# PCM5102.net
KiCad netlist of a schematic drawn in Altium Designer
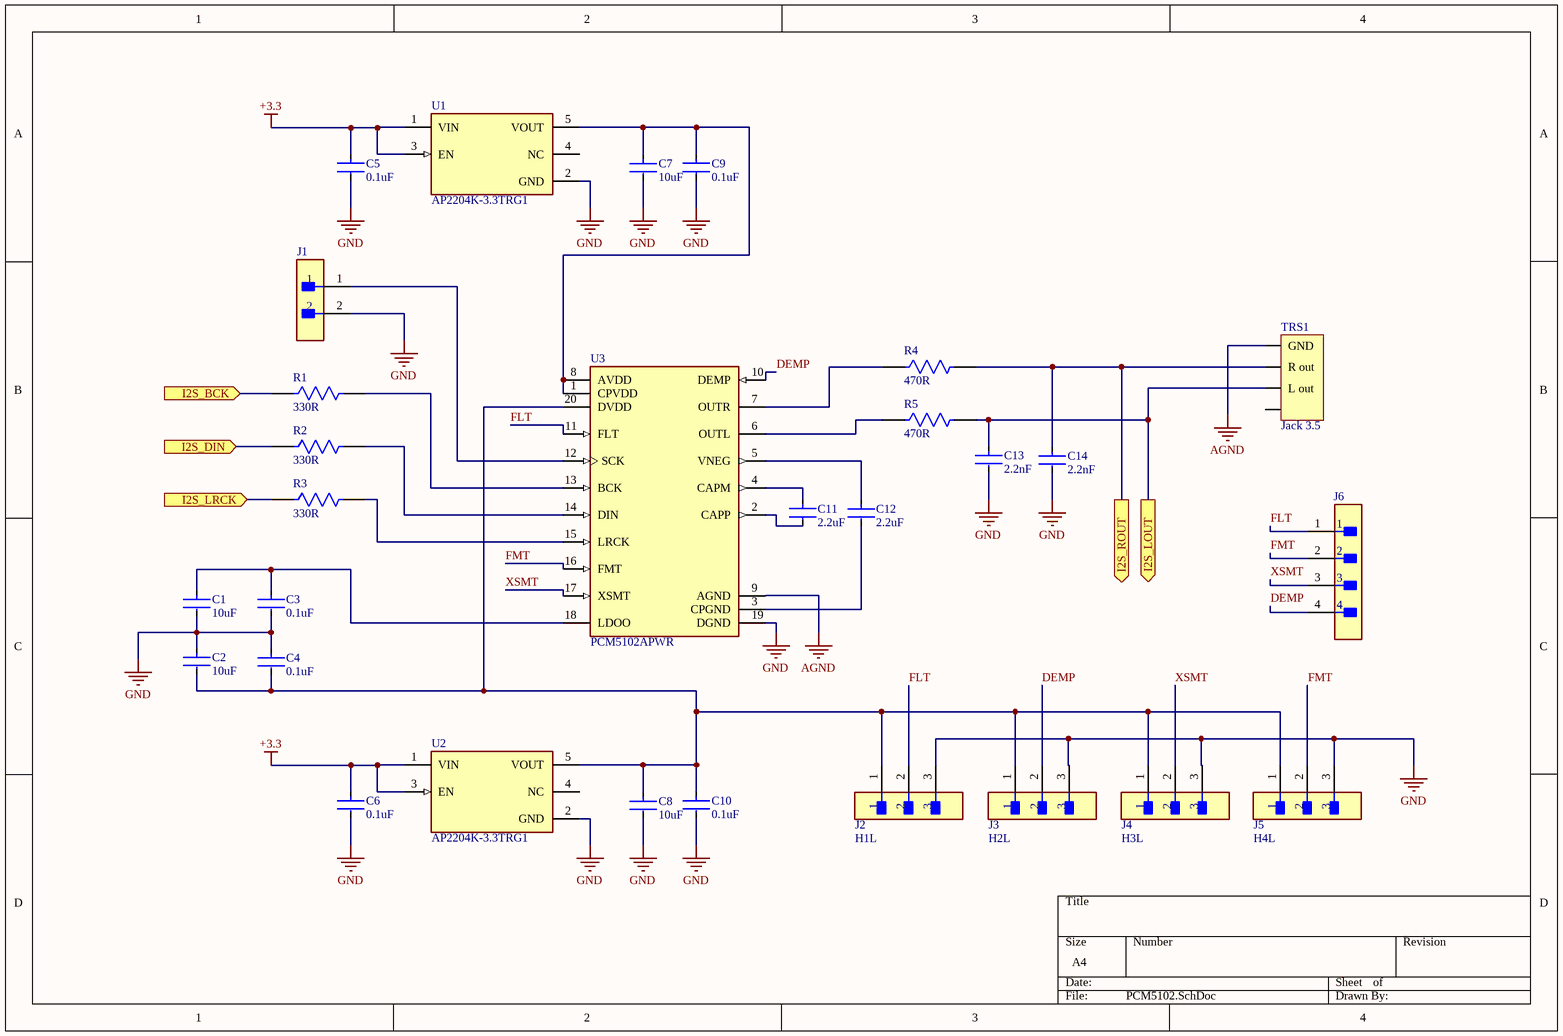
[diagram p0: PCM5102.SchDoc]

(export (version "E")
  (design (tool "Eeschema 10.0.6"))
  (components
    (comp (ref "C1")
      (value "10uF")
      (footprint "FP-CL21-IPC_C")
      (description "CL21 Series 0805 47nF 50V ±5% Tolerance X7R Multilayer Ceramic Chip Capacitor")
      (fields (field (name "TOLERANCE") "5%"))
      (libsource (lib "Altium Content Vault") (part "b4654b650e69147ec39a6b967a45e02"))
    )
    (comp (ref "C2")
      (value "10uF")
      (footprint "FP-CL21-IPC_C")
      (description "CL21 Series 0805 47nF 50V ±5% Tolerance X7R Multilayer Ceramic Chip Capacitor")
      (fields (field (name "TOLERANCE") "5%"))
      (libsource (lib "Altium Content Vault") (part "b4654b650e69147ec39a6b967a45e02"))
    )
    (comp (ref "C3")
      (value "0.1uF")
      (footprint "FP-CL21-IPC_C")
      (description "CL21 Series 0805 47nF 50V ±5% Tolerance X7R Multilayer Ceramic Chip Capacitor")
      (fields (field (name "TOLERANCE") "5%"))
      (libsource (lib "Altium Content Vault") (part "b4654b650e69147ec39a6b967a45e02"))
    )
    (comp (ref "C4")
      (value "0.1uF")
      (footprint "FP-CL21-IPC_C")
      (description "CL21 Series 0805 47nF 50V ±5% Tolerance X7R Multilayer Ceramic Chip Capacitor")
      (fields (field (name "TOLERANCE") "5%"))
      (libsource (lib "Altium Content Vault") (part "b4654b650e69147ec39a6b967a45e02"))
    )
    (comp (ref "C5")
      (value "0.1uF")
      (footprint "FP-CL21-IPC_C")
      (description "CL21 Series 0805 47nF 50V ±5% Tolerance X7R Multilayer Ceramic Chip Capacitor")
      (fields (field (name "TOLERANCE") "5%"))
      (libsource (lib "Altium Content Vault") (part "b4654b650e69147ec39a6b967a45e02"))
    )
    (comp (ref "C6")
      (value "0.1uF")
      (footprint "FP-CL21-IPC_C")
      (description "CL21 Series 0805 47nF 50V ±5% Tolerance X7R Multilayer Ceramic Chip Capacitor")
      (fields (field (name "TOLERANCE") "5%"))
      (libsource (lib "Altium Content Vault") (part "b4654b650e69147ec39a6b967a45e02"))
    )
    (comp (ref "C7")
      (value "10uF")
      (footprint "FP-CL21-IPC_C")
      (description "CL21 Series 0805 47nF 50V ±5% Tolerance X7R Multilayer Ceramic Chip Capacitor")
      (fields (field (name "TOLERANCE") "5%"))
      (libsource (lib "Altium Content Vault") (part "b4654b650e69147ec39a6b967a45e02"))
    )
    (comp (ref "C8")
      (value "10uF")
      (footprint "FP-CL21-IPC_C")
      (description "CL21 Series 0805 47nF 50V ±5% Tolerance X7R Multilayer Ceramic Chip Capacitor")
      (fields (field (name "TOLERANCE") "5%"))
      (libsource (lib "Altium Content Vault") (part "b4654b650e69147ec39a6b967a45e02"))
    )
    (comp (ref "C9")
      (value "0.1uF")
      (footprint "FP-CL21-IPC_C")
      (description "CL21 Series 0805 47nF 50V ±5% Tolerance X7R Multilayer Ceramic Chip Capacitor")
      (fields (field (name "TOLERANCE") "5%"))
      (libsource (lib "Altium Content Vault") (part "b4654b650e69147ec39a6b967a45e02"))
    )
    (comp (ref "C10")
      (value "0.1uF")
      (footprint "FP-CL21-IPC_C")
      (description "CL21 Series 0805 47nF 50V ±5% Tolerance X7R Multilayer Ceramic Chip Capacitor")
      (fields (field (name "TOLERANCE") "5%"))
      (libsource (lib "Altium Content Vault") (part "b4654b650e69147ec39a6b967a45e02"))
    )
    (comp (ref "C11")
      (value "2.2uF")
      (footprint "FP-CL21-IPC_C")
      (description "CL21 Series 0805 47nF 50V ±5% Tolerance X7R Multilayer Ceramic Chip Capacitor")
      (fields (field (name "TOLERANCE") "5%"))
      (libsource (lib "Altium Content Vault") (part "b4654b650e69147ec39a6b967a45e02"))
    )
    (comp (ref "C12")
      (value "2.2uF")
      (footprint "FP-CL21-IPC_C")
      (description "CL21 Series 0805 47nF 50V ±5% Tolerance X7R Multilayer Ceramic Chip Capacitor")
      (fields (field (name "TOLERANCE") "5%"))
      (libsource (lib "Altium Content Vault") (part "b4654b650e69147ec39a6b967a45e02"))
    )
    (comp (ref "C13")
      (value "2.2nF")
      (footprint "FP-CL21-IPC_C")
      (description "CL21 Series 0805 47nF 50V ±5% Tolerance X7R Multilayer Ceramic Chip Capacitor")
      (fields (field (name "TOLERANCE") "5%"))
      (libsource (lib "Altium Content Vault") (part "b4654b650e69147ec39a6b967a45e02"))
    )
    (comp (ref "C14")
      (value "2.2nF")
      (footprint "FP-CL21-IPC_C")
      (description "CL21 Series 0805 47nF 50V ±5% Tolerance X7R Multilayer Ceramic Chip Capacitor")
      (fields (field (name "TOLERANCE") "5%"))
      (libsource (lib "Altium Content Vault") (part "b4654b650e69147ec39a6b967a45e02"))
    )
    (comp (ref "J1")
      (value "M22-2510205")
      (footprint "FP-M22-2510205-MFG")
      (description "CONN HEADER VERT 2POS 2MM")
      (fields
        (field (name "MANUFACTURER") "Harwin")
        (field (name "OCTOPART") "https://octopart.com/m22-2510205-harwin-2538221")
      )
      (libsource (lib "Altium Content Vault") (part "3bc925449376181038e59eaffc5286c"))
    )
    (comp (ref "J2")
      (value "H1L")
      (footprint "FP-951103-8622-AR-MFG")
      (description "CONN HEADER VERT 3POS 2MM")
      (fields
        (field (name "MANUFACTURER PART NUMBER") "951103-8622-AR")
        (field (name "OCTOPART") "https://octopart.com/951103-8622-ar-3m-14400669")
      )
      (libsource (lib "Altium Content Vault") (part "0d3f023dd272f625e17a2be33dea85f"))
    )
    (comp (ref "J3")
      (value "H2L")
      (footprint "FP-951103-8622-AR-MFG")
      (description "CONN HEADER VERT 3POS 2MM")
      (fields
        (field (name "MANUFACTURER PART NUMBER") "951103-8622-AR")
        (field (name "OCTOPART") "https://octopart.com/951103-8622-ar-3m-14400669")
      )
      (libsource (lib "Altium Content Vault") (part "0d3f023dd272f625e17a2be33dea85f"))
    )
    (comp (ref "J4")
      (value "H3L")
      (footprint "FP-951103-8622-AR-MFG")
      (description "CONN HEADER VERT 3POS 2MM")
      (fields
        (field (name "MANUFACTURER PART NUMBER") "951103-8622-AR")
        (field (name "OCTOPART") "https://octopart.com/951103-8622-ar-3m-14400669")
      )
      (libsource (lib "Altium Content Vault") (part "0d3f023dd272f625e17a2be33dea85f"))
    )
    (comp (ref "J5")
      (value "H4L")
      (footprint "FP-951103-8622-AR-MFG")
      (description "CONN HEADER VERT 3POS 2MM")
      (fields
        (field (name "MANUFACTURER PART NUMBER") "951103-8622-AR")
        (field (name "OCTOPART") "https://octopart.com/951103-8622-ar-3m-14400669")
      )
      (libsource (lib "Altium Content Vault") (part "0d3f023dd272f625e17a2be33dea85f"))
    )
    (comp (ref "J6")
      (value "M20-9990445")
      (footprint "FP-M20-9990445-MFG")
      (description "M20-9990445 Conn Unshrouded Header HDR 4 POS 2.54mm Solder ST Thru-Hole Bulk/Loose")
      (libsource (lib "Altium Content Vault") (part "299a8cea1bdcbc3624fe62c390fa72c"))
    )
    (comp (ref "R1")
      (value "330R")
      (footprint "FP-RP732A-IPC_C")
      (fields (field (name "TOLERANCE") "0.1%"))
      (libsource (lib "Altium Content Vault") (part "1029c3af85768c4190bb7ad29bc67b5"))
    )
    (comp (ref "R2")
      (value "330R")
      (footprint "FP-RP732A-IPC_C")
      (fields (field (name "TOLERANCE") "0.1%"))
      (libsource (lib "Altium Content Vault") (part "1029c3af85768c4190bb7ad29bc67b5"))
    )
    (comp (ref "R3")
      (value "330R")
      (footprint "FP-RP732A-IPC_C")
      (fields (field (name "TOLERANCE") "0.1%"))
      (libsource (lib "Altium Content Vault") (part "1029c3af85768c4190bb7ad29bc67b5"))
    )
    (comp (ref "R4")
      (value "470R")
      (footprint "FP-RP732A-IPC_C")
      (fields (field (name "TOLERANCE") "0.1%"))
      (libsource (lib "Altium Content Vault") (part "1029c3af85768c4190bb7ad29bc67b5"))
    )
    (comp (ref "R5")
      (value "470R")
      (footprint "FP-RP732A-IPC_C")
      (fields (field (name "TOLERANCE") "0.1%"))
      (libsource (lib "Altium Content Vault") (part "1029c3af85768c4190bb7ad29bc67b5"))
    )
    (comp (ref "TRS1")
      (value "Jack 3.5")
      (footprint "PJ-327A")
      (libsource (lib "Schemati_design") (part "PJ327A"))
    )
    (comp (ref "U1")
      (value "AP2204K-3.3TRG1")
      (footprint "FP-SOT25-IPC_C")
      (description "IC REG LINEAR 3.3V 150MA SOT23-5")
      (libsource (lib "Altium Content Vault") (part "038a824adfd04a965d73cdd9fb88cf2"))
    )
    (comp (ref "U2")
      (value "AP2204K-3.3TRG1")
      (footprint "FP-SOT25-IPC_C")
      (description "IC REG LINEAR 3.3V 150MA SOT23-5")
      (libsource (lib "Altium Content Vault") (part "038a824adfd04a965d73cdd9fb88cf2"))
    )
    (comp (ref "U3")
      (value "PCM5102APWR")
      (footprint "FP-PW0020A-IPC_A")
      (description "IC DAC 16/24/32BIT 384K 20TSSOP")
      (libsource (lib "Altium Content Vault") (part "831166dc95f78e7a0e4986cce343839"))
    )
  )
  (nets
    (net (code "1") (name "+3.3") (class "Default")
      (node (ref "C5") (pin "1") (pinfunction "1_1") (pintype "passive"))
      (node (ref "C6") (pin "1") (pinfunction "1_1") (pintype "passive"))
      (node (ref "U1") (pin "1") (pinfunction "VIN_1") (pintype "power_in"))
      (node (ref "U1") (pin "3") (pinfunction "EN_3") (pintype "input"))
      (node (ref "U2") (pin "1") (pinfunction "VIN_1") (pintype "power_in"))
      (node (ref "U2") (pin "3") (pinfunction "EN_3") (pintype "input"))
    )
    (net (code "2") (name "/DEMP") (class "Default")
      (node (ref "J3") (pin "2") (pinfunction "2_2") (pintype "passive"))
      (node (ref "J6") (pin "4") (pinfunction "4_4") (pintype "passive"))
      (node (ref "U3") (pin "10") (pinfunction "DEMP_10") (pintype "input"))
    )
    (net (code "3") (name "/FLT") (class "Default")
      (node (ref "J2") (pin "2") (pinfunction "2_2") (pintype "passive"))
      (node (ref "J6") (pin "1") (pinfunction "1_1") (pintype "passive"))
      (node (ref "U3") (pin "11") (pinfunction "FLT_11") (pintype "input"))
    )
    (net (code "4") (name "/FMT") (class "Default")
      (node (ref "J5") (pin "2") (pinfunction "2_2") (pintype "passive"))
      (node (ref "J6") (pin "2") (pinfunction "2_2") (pintype "passive"))
      (node (ref "U3") (pin "16") (pinfunction "FMT_16") (pintype "input"))
    )
    (net (code "5") (name "/I2S_BCK") (class "Default")
      (node (ref "R1") (pin "1") (pinfunction "1_1") (pintype "passive"))
    )
    (net (code "6") (name "/I2S_DIN") (class "Default")
      (node (ref "R2") (pin "1") (pinfunction "1_1") (pintype "passive"))
    )
    (net (code "7") (name "/I2S_LOUT") (class "Default")
      (node (ref "C13") (pin "1") (pinfunction "1_1") (pintype "passive"))
      (node (ref "R5") (pin "2") (pinfunction "2_2") (pintype "passive"))
      (node (ref "TRS1") (pin "3") (pinfunction "L_out_3") (pintype "passive"))
    )
    (net (code "8") (name "/I2S_LRCK") (class "Default")
      (node (ref "R3") (pin "1") (pinfunction "1_1") (pintype "passive"))
    )
    (net (code "9") (name "/I2S_ROUT") (class "Default")
      (node (ref "C14") (pin "1") (pinfunction "1_1") (pintype "passive"))
      (node (ref "R4") (pin "2") (pinfunction "2_2") (pintype "passive"))
      (node (ref "TRS1") (pin "2") (pinfunction "R_out_2") (pintype "passive"))
    )
    (net (code "10") (name "/XSMT") (class "Default")
      (node (ref "J4") (pin "2") (pinfunction "2_2") (pintype "passive"))
      (node (ref "J6") (pin "3") (pinfunction "3_3") (pintype "passive"))
      (node (ref "U3") (pin "17") (pinfunction "XSMT_17") (pintype "input"))
    )
    (net (code "11") (name "AGND") (class "Default")
      (node (ref "TRS1") (pin "1") (pinfunction "GND_1") (pintype "passive"))
      (node (ref "U3") (pin "9") (pinfunction "AGND_9") (pintype "power_in"))
    )
    (net (code "12") (name "GND") (class "Default")
      (node (ref "C1") (pin "2") (pinfunction "2_2") (pintype "passive"))
      (node (ref "C10") (pin "2") (pinfunction "2_2") (pintype "passive"))
      (node (ref "C13") (pin "2") (pinfunction "2_2") (pintype "passive"))
      (node (ref "C14") (pin "2") (pinfunction "2_2") (pintype "passive"))
      (node (ref "C2") (pin "1") (pinfunction "1_1") (pintype "passive"))
      (node (ref "C3") (pin "2") (pinfunction "2_2") (pintype "passive"))
      (node (ref "C4") (pin "1") (pinfunction "1_1") (pintype "passive"))
      (node (ref "C5") (pin "2") (pinfunction "2_2") (pintype "passive"))
      (node (ref "C6") (pin "2") (pinfunction "2_2") (pintype "passive"))
      (node (ref "C7") (pin "2") (pinfunction "2_2") (pintype "passive"))
      (node (ref "C8") (pin "2") (pinfunction "2_2") (pintype "passive"))
      (node (ref "C9") (pin "2") (pinfunction "2_2") (pintype "passive"))
      (node (ref "J1") (pin "2") (pinfunction "2_2") (pintype "passive"))
      (node (ref "J2") (pin "3") (pinfunction "3_3") (pintype "passive"))
      (node (ref "J3") (pin "3") (pinfunction "3_3") (pintype "passive"))
      (node (ref "J4") (pin "3") (pinfunction "3_3") (pintype "passive"))
      (node (ref "J5") (pin "3") (pinfunction "3_3") (pintype "passive"))
      (node (ref "U1") (pin "2") (pinfunction "GND_2") (pintype "power_in"))
      (node (ref "U2") (pin "2") (pinfunction "GND_2") (pintype "power_in"))
      (node (ref "U3") (pin "19") (pinfunction "DGND_19") (pintype "power_in"))
    )
    (net (code "13") (name "Net-(U1-VOUT)") (class "Default")
      (node (ref "C7") (pin "1") (pinfunction "1_1") (pintype "passive"))
      (node (ref "C9") (pin "1") (pinfunction "1_1") (pintype "passive"))
      (node (ref "U1") (pin "5") (pinfunction "VOUT_5") (pintype "power_in"))
      (node (ref "U3") (pin "1") (pinfunction "CPVDD_1") (pintype "power_in"))
      (node (ref "U3") (pin "8") (pinfunction "AVDD_8") (pintype "power_in"))
    )
    (net (code "14") (name "Net-(U2-VOUT)") (class "Default")
      (node (ref "C10") (pin "1") (pinfunction "1_1") (pintype "passive"))
      (node (ref "C2") (pin "2") (pinfunction "2_2") (pintype "passive"))
      (node (ref "C4") (pin "2") (pinfunction "2_2") (pintype "passive"))
      (node (ref "C8") (pin "1") (pinfunction "1_1") (pintype "passive"))
      (node (ref "J2") (pin "1") (pinfunction "1_1") (pintype "passive"))
      (node (ref "J3") (pin "1") (pinfunction "1_1") (pintype "passive"))
      (node (ref "J4") (pin "1") (pinfunction "1_1") (pintype "passive"))
      (node (ref "J5") (pin "1") (pinfunction "1_1") (pintype "passive"))
      (node (ref "U2") (pin "5") (pinfunction "VOUT_5") (pintype "power_in"))
      (node (ref "U3") (pin "20") (pinfunction "DVDD_20") (pintype "power_in"))
    )
    (net (code "15") (name "Net-(U3-BCK)") (class "Default")
      (node (ref "R1") (pin "2") (pinfunction "2_2") (pintype "passive"))
      (node (ref "U3") (pin "13") (pinfunction "BCK_13") (pintype "input"))
    )
    (net (code "16") (name "Net-(U3-CAPM)") (class "Default")
      (node (ref "C11") (pin "1") (pinfunction "1_1") (pintype "passive"))
      (node (ref "U3") (pin "4") (pinfunction "CAPM_4") (pintype "output"))
    )
    (net (code "17") (name "Net-(U3-CAPP)") (class "Default")
      (node (ref "C11") (pin "2") (pinfunction "2_2") (pintype "passive"))
      (node (ref "U3") (pin "2") (pinfunction "CAPP_2") (pintype "output"))
    )
    (net (code "18") (name "Net-(U3-CPGND)") (class "Default")
      (node (ref "C12") (pin "2") (pinfunction "2_2") (pintype "passive"))
      (node (ref "U3") (pin "3") (pinfunction "CPGND_3") (pintype "power_in"))
    )
    (net (code "19") (name "Net-(U3-DIN)") (class "Default")
      (node (ref "R2") (pin "2") (pinfunction "2_2") (pintype "passive"))
      (node (ref "U3") (pin "14") (pinfunction "DIN_14") (pintype "input"))
    )
    (net (code "20") (name "Net-(U3-LDOO)") (class "Default")
      (node (ref "C1") (pin "1") (pinfunction "1_1") (pintype "passive"))
      (node (ref "C3") (pin "1") (pinfunction "1_1") (pintype "passive"))
      (node (ref "U3") (pin "18") (pinfunction "LDOO_18") (pintype "power_in"))
    )
    (net (code "21") (name "Net-(U3-LRCK)") (class "Default")
      (node (ref "R3") (pin "2") (pinfunction "2_2") (pintype "passive"))
      (node (ref "U3") (pin "15") (pinfunction "LRCK_15") (pintype "input"))
    )
    (net (code "22") (name "Net-(U3-OUTL)") (class "Default")
      (node (ref "R5") (pin "1") (pinfunction "1_1") (pintype "passive"))
      (node (ref "U3") (pin "6") (pinfunction "OUTL_6") (pintype "passive"))
    )
    (net (code "23") (name "Net-(U3-OUTR)") (class "Default")
      (node (ref "R4") (pin "1") (pinfunction "1_1") (pintype "passive"))
      (node (ref "U3") (pin "7") (pinfunction "OUTR_7") (pintype "passive"))
    )
    (net (code "24") (name "Net-(U3-SCK)") (class "Default")
      (node (ref "J1") (pin "1") (pinfunction "1_1") (pintype "passive"))
      (node (ref "U3") (pin "12") (pinfunction "SCK_12") (pintype "input"))
    )
    (net (code "25") (name "Net-(U3-VNEG)") (class "Default")
      (node (ref "C12") (pin "1") (pinfunction "1_1") (pintype "passive"))
      (node (ref "U3") (pin "5") (pinfunction "VNEG_5") (pintype "output"))
    )
    (net (code "26") (name "unconnected-(TRS1-Pad4)") (class "Default")
      (node (ref "TRS1") (pin "4") (pinfunction "4_4") (pintype "passive"))
    )
    (net (code "27") (name "unconnected-(U1-NC-Pad4)") (class "Default")
      (node (ref "U1") (pin "4") (pinfunction "NC_4") (pintype "passive"))
    )
    (net (code "28") (name "unconnected-(U2-NC-Pad4)") (class "Default")
      (node (ref "U2") (pin "4") (pinfunction "NC_4") (pintype "passive"))
    )
  )
)
